# Sheet1.net
KiCad netlist of a schematic drawn in Altium Designer
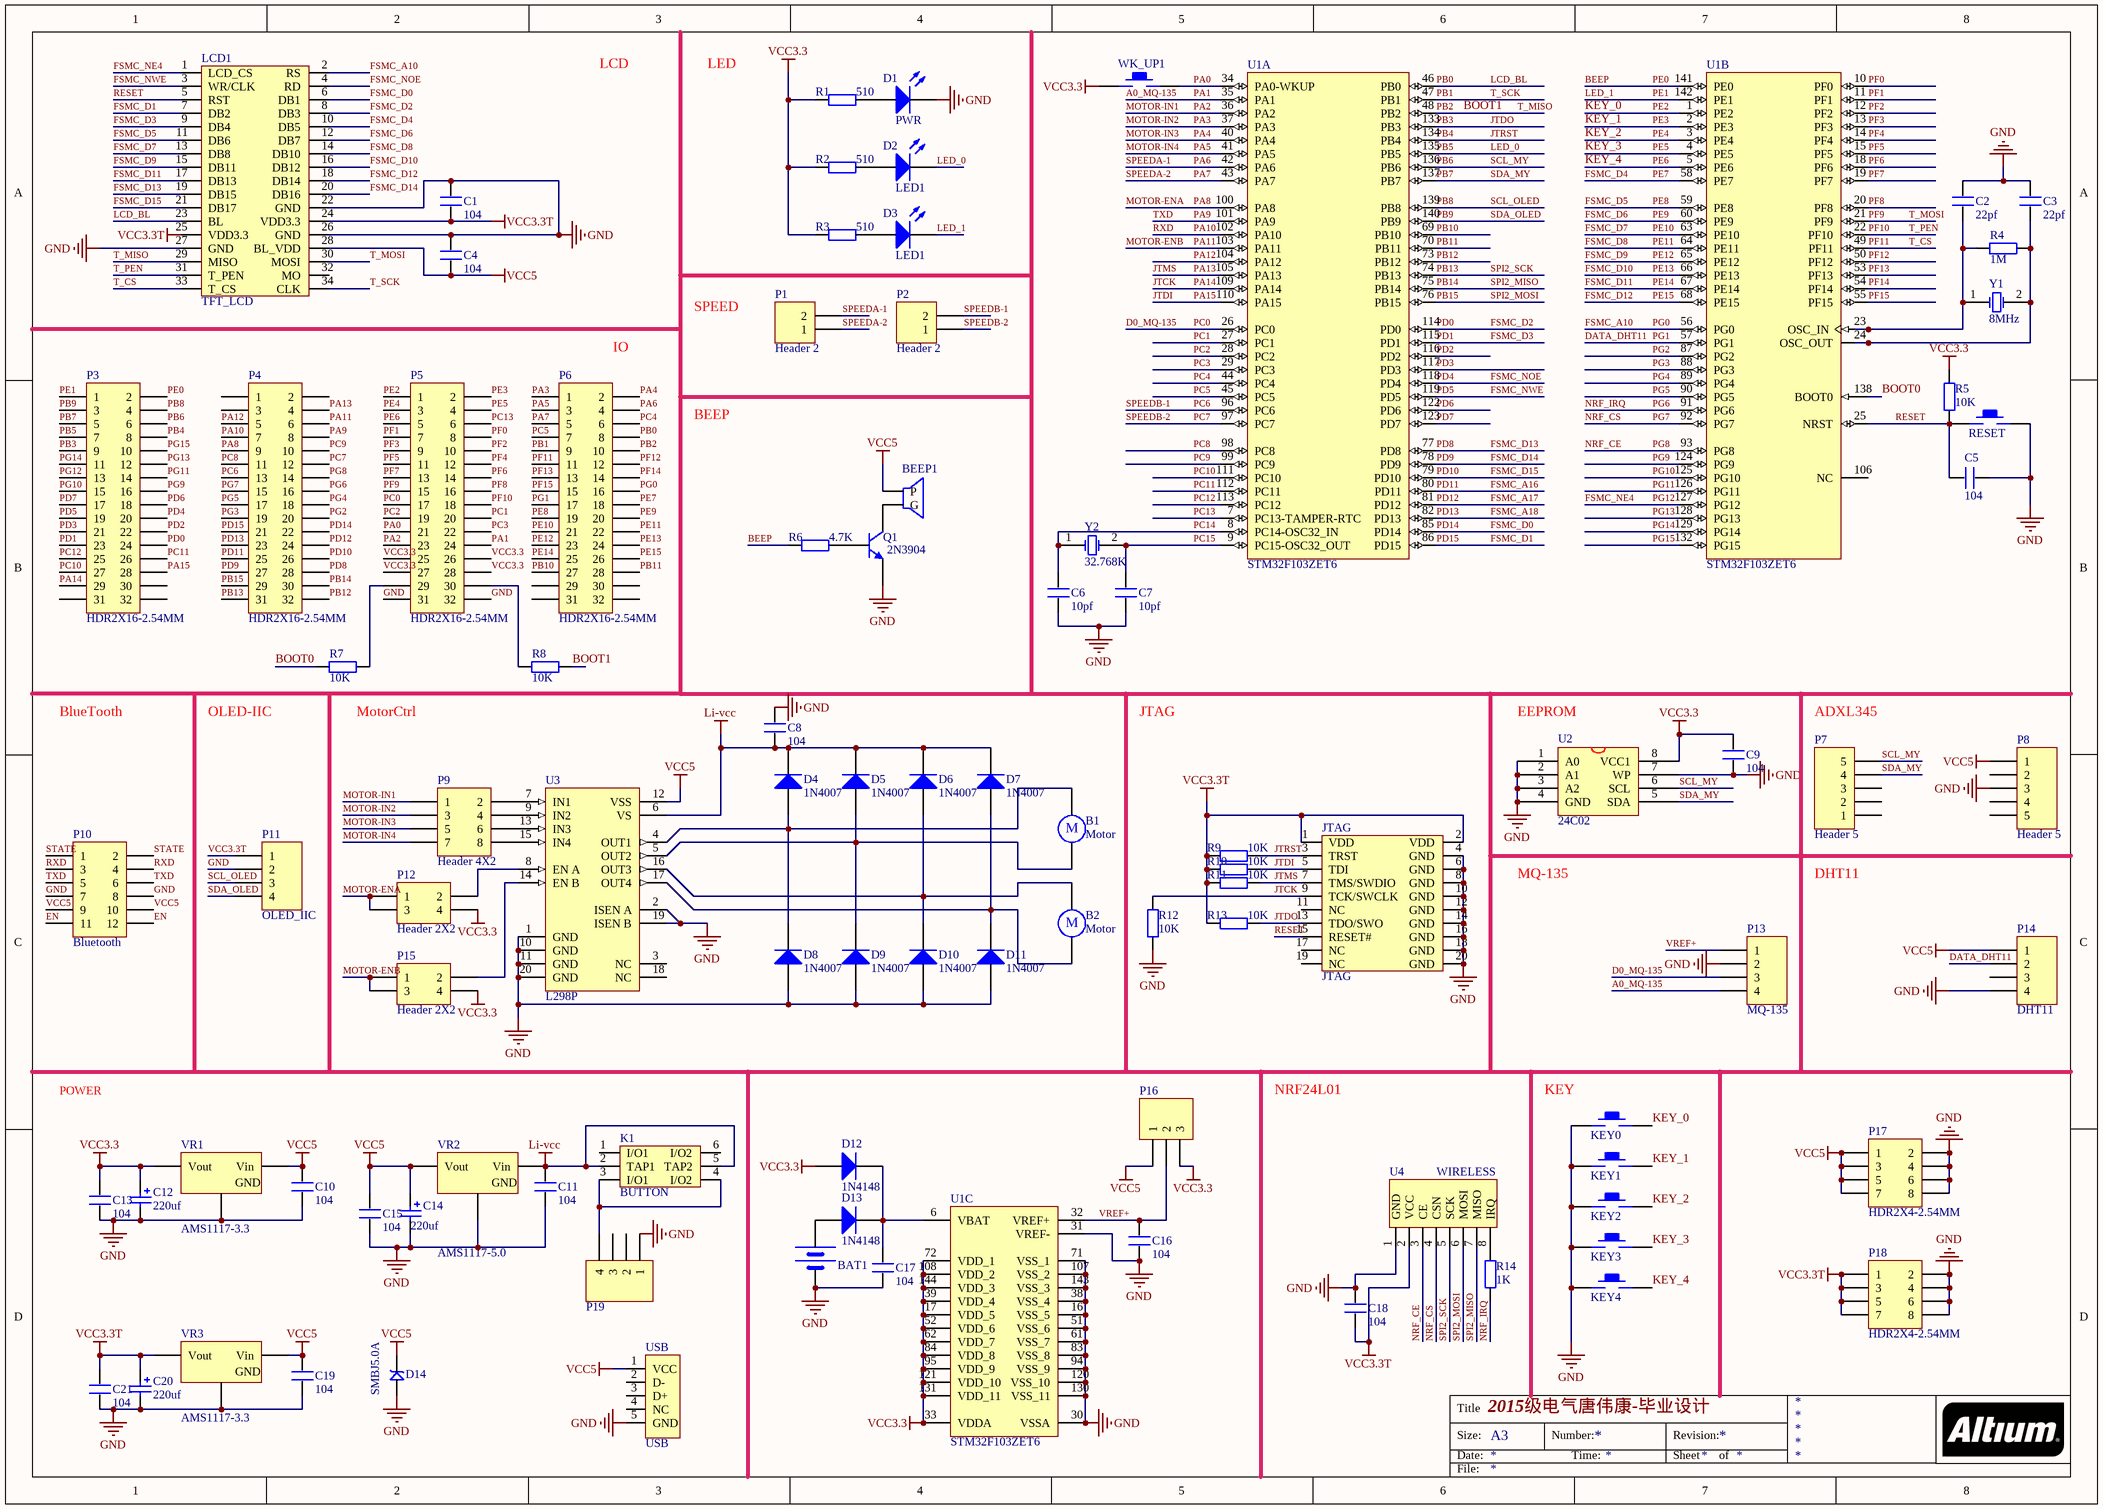
[diagram p0: Sheet1.SchDoc]

(export (version "E")
  (design (tool "Eeschema 10.0.6"))
  (components
    (comp (ref "B1")
      (value "Motor")
      (footprint "RB5-10.5")
      (description "Motor, General Kind")
      (fields (field (name "PUBLISHER") "Altium Limited"))
      (libsource (lib "Miscellaneous Devices") (part "Motor"))
    )
    (comp (ref "B2")
      (value "Motor")
      (footprint "RB5-10.5")
      (description "Motor, General Kind")
      (fields (field (name "PUBLISHER") "Altium Limited"))
      (libsource (lib "Miscellaneous Devices") (part "Motor"))
    )
    (comp (ref "BAT1") (value "BATT") (footprint "BATM") (libsource (lib "MiniSTM32 V3.0封装库") (part "BAT")))
    (comp (ref "BEEP1")
      (value "BEEP")
      (footprint "BELL-5")
      (libsource (lib "WarShip V3 STM32103封装库") (part "BEEP"))
    )
    (comp (ref "C1") (value "104") (footprint "0805") (libsource (lib "WarShip V3 STM32103封装库") (part "C")))
    (comp (ref "C2") (value "22pf") (footprint "0805") (libsource (lib "WarShip V3 STM32103封装库") (part "C")))
    (comp (ref "C3") (value "22pf") (footprint "0805") (libsource (lib "WarShip V3 STM32103封装库") (part "C")))
    (comp (ref "C4") (value "104") (footprint "0805") (libsource (lib "WarShip V3 STM32103封装库") (part "C")))
    (comp (ref "C5") (value "104") (footprint "0805") (libsource (lib "WarShip V3 STM32103封装库") (part "C")))
    (comp (ref "C6") (value "10pf") (footprint "0805") (libsource (lib "WarShip V3 STM32103封装库") (part "C")))
    (comp (ref "C7") (value "10pf") (footprint "0805") (libsource (lib "WarShip V3 STM32103封装库") (part "C")))
    (comp (ref "C8")
      (value "104")
      (footprint "0805")
      (description "10uf")
      (libsource (lib "WarShip V3 STM32103封装库") (part "C"))
    )
    (comp (ref "C9") (value "104") (footprint "0805") (libsource (lib "WarShip V3 STM32103封装库") (part "C")))
    (comp (ref "C10")
      (value "104")
      (footprint "0805")
      (description "10uf")
      (libsource (lib "WarShip V3 STM32103封装库") (part "C"))
    )
    (comp (ref "C11")
      (value "104")
      (footprint "0805")
      (description "10uf")
      (libsource (lib "WarShip V3 STM32103封装库") (part "C"))
    )
    (comp (ref "C12")
      (value "220uf")
      (footprint "C-DIP-6.3*15")
      (description "*C-DIP-6.3*15")
      (libsource (lib "直插电容 6.3x15封装") (part "C-DIP-6.3*15"))
    )
    (comp (ref "C13") (value "104") (footprint "0805") (libsource (lib "WarShip V3 STM32103封装库") (part "C")))
    (comp (ref "C14")
      (value "220uf")
      (footprint "C-DIP-6.3*15")
      (description "*C-DIP-6.3*15")
      (libsource (lib "直插电容 6.3x15封装") (part "C-DIP-6.3*15"))
    )
    (comp (ref "C15") (value "104") (footprint "0805") (libsource (lib "WarShip V3 STM32103封装库") (part "C")))
    (comp (ref "C16")
      (value "104")
      (footprint "0805")
      (description "10uf")
      (libsource (lib "WarShip V3 STM32103封装库") (part "C"))
    )
    (comp (ref "C17") (value "104") (footprint "0805") (libsource (lib "WarShip V3 STM32103封装库") (part "C")))
    (comp (ref "C18") (value "104") (footprint "0805") (libsource (lib "WarShip V3 STM32103封装库") (part "C")))
    (comp (ref "C19") (value "104") (footprint "0805") (libsource (lib "WarShip V3 STM32103封装库") (part "C")))
    (comp (ref "C20")
      (value "220uf")
      (footprint "C-DIP-6.3*15")
      (description "*C-DIP-6.3*15")
      (libsource (lib "直插电容 6.3x15封装") (part "C-DIP-6.3*15"))
    )
    (comp (ref "C21") (value "104") (footprint "0805") (libsource (lib "WarShip V3 STM32103封装库") (part "C")))
    (comp (ref "D1")
      (value "PWR")
      (footprint "LED-1")
      (description "Typical RED GaAs LED")
      (fields (field (name "PUBLISHER") "Altium Limited"))
      (libsource (lib "Miscellaneous Devices") (part "LED1"))
    )
    (comp (ref "D2")
      (value "LED1")
      (footprint "LED-1")
      (description "Typical RED GaAs LED")
      (fields (field (name "PUBLISHER") "Altium Limited"))
      (libsource (lib "Miscellaneous Devices") (part "LED1"))
    )
    (comp (ref "D3")
      (value "LED1")
      (footprint "LED-1")
      (description "Typical RED GaAs LED")
      (fields (field (name "PUBLISHER") "Altium Limited"))
      (libsource (lib "Miscellaneous Devices") (part "LED1"))
    )
    (comp (ref "D4")
      (value "1N4007")
      (footprint "DO-41")
      (description "1 Amp General Purpose Rectifier")
      (fields (field (name "PUBLISHER") "Altium Limited"))
      (libsource (lib "Miscellaneous Devices") (part "Diode 1N4007"))
    )
    (comp (ref "D5")
      (value "1N4007")
      (footprint "DO-41")
      (description "1 Amp General Purpose Rectifier")
      (fields (field (name "PUBLISHER") "Altium Limited"))
      (libsource (lib "Miscellaneous Devices") (part "Diode 1N4007"))
    )
    (comp (ref "D6")
      (value "1N4007")
      (footprint "DO-41")
      (description "1 Amp General Purpose Rectifier")
      (fields (field (name "PUBLISHER") "Altium Limited"))
      (libsource (lib "Miscellaneous Devices") (part "Diode 1N4007"))
    )
    (comp (ref "D7")
      (value "1N4007")
      (footprint "DO-41")
      (description "1 Amp General Purpose Rectifier")
      (fields (field (name "PUBLISHER") "Altium Limited"))
      (libsource (lib "Miscellaneous Devices") (part "Diode 1N4007"))
    )
    (comp (ref "D8")
      (value "1N4007")
      (footprint "DO-41")
      (description "1 Amp General Purpose Rectifier")
      (fields (field (name "PUBLISHER") "Altium Limited"))
      (libsource (lib "Miscellaneous Devices") (part "Diode 1N4007"))
    )
    (comp (ref "D9")
      (value "1N4007")
      (footprint "DO-41")
      (description "1 Amp General Purpose Rectifier")
      (fields (field (name "PUBLISHER") "Altium Limited"))
      (libsource (lib "Miscellaneous Devices") (part "Diode 1N4007"))
    )
    (comp (ref "D10")
      (value "1N4007")
      (footprint "DO-41")
      (description "1 Amp General Purpose Rectifier")
      (fields (field (name "PUBLISHER") "Altium Limited"))
      (libsource (lib "Miscellaneous Devices") (part "Diode 1N4007"))
    )
    (comp (ref "D11")
      (value "1N4007")
      (footprint "DO-41")
      (description "1 Amp General Purpose Rectifier")
      (fields (field (name "PUBLISHER") "Altium Limited"))
      (libsource (lib "Miscellaneous Devices") (part "Diode 1N4007"))
    )
    (comp (ref "D12")
      (value "1N4148")
      (footprint "DO-35")
      (description "High Conductance Fast Diode")
      (fields (field (name "PUBLISHER") "Altium Limited"))
      (libsource (lib "Miscellaneous Devices") (part "Diode 1N4148"))
    )
    (comp (ref "D13")
      (value "1N4148")
      (footprint "DO-35")
      (description "High Conductance Fast Diode")
      (fields (field (name "PUBLISHER") "Altium Limited"))
      (libsource (lib "Miscellaneous Devices") (part "Diode 1N4148"))
    )
    (comp (ref "D14")
      (value "SMBJ5.0A")
      (footprint "SMBJ")
      (description "TVS")
      (libsource (lib "MiniSTM32 V3.0封装库") (part "SMBJ"))
    )
    (comp (ref "JTAG")
      (value "JTAG")
      (footprint "JTAG_20")
      (libsource (lib "WarShip V3 STM32103封装库") (part "JTAG"))
    )
    (comp (ref "K1")
      (value "BUTTON")
      (footprint "BTN8.5*8.5")
      (libsource (lib "WarShip V3 STM32103封装库") (part "BUTTON"))
    )
    (comp (ref "KEY0")
      (value "KEY0")
      (footprint "KEY_M")
      (libsource (lib "MiniSTM32 V3.0封装库") (part "KEY_M"))
    )
    (comp (ref "KEY1")
      (value "KEY1")
      (footprint "KEY_M")
      (libsource (lib "MiniSTM32 V3.0封装库") (part "KEY_M"))
    )
    (comp (ref "KEY2")
      (value "KEY2")
      (footprint "KEY_M")
      (libsource (lib "MiniSTM32 V3.0封装库") (part "KEY_M"))
    )
    (comp (ref "KEY3")
      (value "KEY2")
      (footprint "KEY_M")
      (libsource (lib "MiniSTM32 V3.0封装库") (part "KEY_M"))
    )
    (comp (ref "KEY4")
      (value "KEY2")
      (footprint "KEY_M")
      (libsource (lib "MiniSTM32 V3.0封装库") (part "KEY_M"))
    )
    (comp (ref "LCD1")
      (value "TFT_LCD")
      (footprint "db2*17-4.3")
      (libsource (lib "WarShip V3 STM32103封装库") (part "TFT_LCD"))
    )
    (comp (ref "P1")
      (value "Header 2")
      (footprint "HDR1X2")
      (description "Header, 2-Pin")
      (fields (field (name "PUBLISHER") "Altium Limited"))
      (libsource (lib "Miscellaneous Connectors") (part "Header 2"))
    )
    (comp (ref "P2")
      (value "Header 2")
      (footprint "HDR1X2")
      (description "Header, 2-Pin")
      (fields (field (name "PUBLISHER") "Altium Limited"))
      (libsource (lib "Miscellaneous Connectors") (part "Header 2"))
    )
    (comp (ref "P3")
      (value "HDR2X16-2.54MM")
      (footprint "HDR2X16-2.54MM")
      (fields (field (name "DESIGNER") "www.dratk.com"))
      (libsource (lib "HDR2X16-2.54MM") (part "HDR2X16-2.54MM"))
    )
    (comp (ref "P4")
      (value "HDR2X16-2.54MM")
      (footprint "HDR2X16-2.54MM")
      (fields (field (name "DESIGNER") "www.dratk.com"))
      (libsource (lib "HDR2X16-2.54MM") (part "HDR2X16-2.54MM"))
    )
    (comp (ref "P5")
      (value "HDR2X16-2.54MM")
      (footprint "HDR2X16-2.54MM")
      (fields (field (name "DESIGNER") "www.dratk.com"))
      (libsource (lib "HDR2X16-2.54MM") (part "HDR2X16-2.54MM"))
    )
    (comp (ref "P6")
      (value "HDR2X16-2.54MM")
      (footprint "HDR2X16-2.54MM")
      (fields (field (name "DESIGNER") "www.dratk.com"))
      (libsource (lib "HDR2X16-2.54MM") (part "HDR2X16-2.54MM"))
    )
    (comp (ref "P7")
      (value "Header 5")
      (footprint "HDR1X5")
      (description "Header, 5-Pin")
      (fields (field (name "PUBLISHER") "Altium Limited"))
      (libsource (lib "Miscellaneous Connectors") (part "Header 5"))
    )
    (comp (ref "P8")
      (value "Header 5")
      (footprint "HDR1X5")
      (description "Header, 5-Pin")
      (fields (field (name "PUBLISHER") "Altium Limited"))
      (libsource (lib "") (part "Header 5_1"))
    )
    (comp (ref "P9")
      (value "Header 4X2")
      (footprint "HDR2X4")
      (description "Header, 4-Pin, Dual row")
      (fields (field (name "PUBLISHER") "Altium Limited"))
      (libsource (lib "Miscellaneous Connectors") (part "Header 4X2"))
    )
    (comp (ref "P10")
      (value "Bluetooth")
      (footprint "Header2X6-2.54MM")
      (fields (field (name "DESIGNER") "www.dratk.com"))
      (libsource (lib "Header2X6-2.54MM") (part "Header2X6-2.54MM"))
    )
    (comp (ref "P11")
      (value "OLED_IIC")
      (footprint "Header1X4-2.54MM")
      (fields (field (name "DESIGNER") "www.dratk.com"))
      (libsource (lib "Header1X4-2.54MM") (part "Header1X4-2.54MM"))
    )
    (comp (ref "P12")
      (value "Header 2X2")
      (footprint "HDR2X2")
      (description "Header, 2-Pin, Dual row")
      (fields (field (name "PUBLISHER") "Altium Limited"))
      (libsource (lib "Miscellaneous Connectors") (part "Header 2X2"))
    )
    (comp (ref "P13")
      (value "MQ-135")
      (footprint "Header1X4-2.54MM")
      (fields (field (name "DESIGNER") "www.dratk.com"))
      (libsource (lib "Header1X4-2.54MM") (part "Header1X4-2.54MM"))
    )
    (comp (ref "P14")
      (value "DHT11")
      (footprint "Header1X4-2.54MM")
      (fields (field (name "DESIGNER") "www.dratk.com"))
      (libsource (lib "Header1X4-2.54MM") (part "Header1X4-2.54MM"))
    )
    (comp (ref "P15")
      (value "Header 2X2")
      (footprint "HDR2X2")
      (description "Header, 2-Pin, Dual row")
      (fields (field (name "PUBLISHER") "Altium Limited"))
      (libsource (lib "Miscellaneous Connectors") (part "Header 2X2"))
    )
    (comp (ref "P16")
      (value "Header 3")
      (footprint "HDR1X3")
      (description "Header, 3-Pin")
      (fields (field (name "PUBLISHER") "Altium Limited"))
      (libsource (lib "Miscellaneous Connectors") (part "Header 3"))
    )
    (comp (ref "P17")
      (value "HDR2X4-2.54MM")
      (footprint "HDR2X4-2.54MM")
      (fields (field (name "DESIGNER") "www.dratk.com"))
      (libsource (lib "HDR2X4-2.54MM") (part "HDR2X4-2.54MM"))
    )
    (comp (ref "P18")
      (value "HDR2X4-2.54MM")
      (footprint "HDR2X4-2.54MM")
      (fields (field (name "DESIGNER") "www.dratk.com"))
      (libsource (lib "HDR2X4-2.54MM") (part "HDR2X4-2.54MM"))
    )
    (comp (ref "P19")
      (value "Header1X4-2.54MM")
      (footprint "Header1X4-2.54MM")
      (fields (field (name "DESIGNER") "www.dratk.com"))
      (libsource (lib "") (part "Header1X4-2.54MM_1"))
    )
    (comp (ref "Q1")
      (value "2N3904")
      (footprint "TO-92A")
      (description "NPN General Purpose Amplifier")
      (fields (field (name "PUBLISHER") "Altium Limited"))
      (libsource (lib "Miscellaneous Devices") (part "2N3904"))
    )
    (comp (ref "R1")
      (value "510")
      (footprint "AXIAL-0.4")
      (description "Resistor")
      (fields (field (name "Comment") "Res2") (field (name "PUBLISHER") "Altium Limited"))
      (libsource (lib "Miscellaneous Devices") (part "Res2"))
    )
    (comp (ref "R2")
      (value "510")
      (footprint "AXIAL-0.4")
      (description "Resistor")
      (fields (field (name "Comment") "Res2") (field (name "PUBLISHER") "Altium Limited"))
      (libsource (lib "Miscellaneous Devices") (part "Res2"))
    )
    (comp (ref "R3")
      (value "510")
      (footprint "AXIAL-0.4")
      (description "Resistor")
      (fields (field (name "Comment") "Res2") (field (name "PUBLISHER") "Altium Limited"))
      (libsource (lib "Miscellaneous Devices") (part "Res2"))
    )
    (comp (ref "R4")
      (value "1M")
      (footprint "AXIAL-0.4")
      (description "Resistor")
      (fields (field (name "Comment") "Res2") (field (name "PUBLISHER") "Altium Limited"))
      (libsource (lib "Miscellaneous Devices") (part "Res2"))
    )
    (comp (ref "R5")
      (value "10K")
      (footprint "AXIAL-0.4")
      (description "Resistor")
      (fields (field (name "Comment") "Res2") (field (name "PUBLISHER") "Altium Limited"))
      (libsource (lib "") (part "Res2_1"))
    )
    (comp (ref "R6")
      (value "4.7K")
      (footprint "AXIAL-0.4")
      (description "Resistor")
      (fields (field (name "Comment") "Res2") (field (name "PUBLISHER") "Altium Limited"))
      (libsource (lib "Miscellaneous Devices") (part "Res2"))
    )
    (comp (ref "R7")
      (value "10K")
      (footprint "AXIAL-0.4")
      (description "Resistor")
      (fields (field (name "Comment") "Res2") (field (name "PUBLISHER") "Altium Limited"))
      (libsource (lib "Miscellaneous Devices") (part "Res2"))
    )
    (comp (ref "R8")
      (value "10K")
      (footprint "AXIAL-0.4")
      (description "Resistor")
      (fields (field (name "Comment") "Res2") (field (name "PUBLISHER") "Altium Limited"))
      (libsource (lib "Miscellaneous Devices") (part "Res2"))
    )
    (comp (ref "R9")
      (value "10K")
      (footprint "AXIAL-0.4")
      (description "Resistor")
      (fields (field (name "Comment") "Res2") (field (name "PUBLISHER") "Altium Limited"))
      (libsource (lib "Miscellaneous Devices") (part "Res2"))
    )
    (comp (ref "R10")
      (value "10K")
      (footprint "AXIAL-0.4")
      (description "Resistor")
      (fields (field (name "Comment") "Res2") (field (name "PUBLISHER") "Altium Limited"))
      (libsource (lib "Miscellaneous Devices") (part "Res2"))
    )
    (comp (ref "R11")
      (value "10K")
      (footprint "AXIAL-0.4")
      (description "Resistor")
      (fields (field (name "Comment") "Res2") (field (name "PUBLISHER") "Altium Limited"))
      (libsource (lib "Miscellaneous Devices") (part "Res2"))
    )
    (comp (ref "R12")
      (value "10K")
      (footprint "AXIAL-0.4")
      (description "Resistor")
      (fields (field (name "Comment") "Res2") (field (name "PUBLISHER") "Altium Limited"))
      (libsource (lib "") (part "Res2_1"))
    )
    (comp (ref "R13")
      (value "10K")
      (footprint "AXIAL-0.4")
      (description "Resistor")
      (fields (field (name "Comment") "Res2") (field (name "PUBLISHER") "Altium Limited"))
      (libsource (lib "Miscellaneous Devices") (part "Res2"))
    )
    (comp (ref "R14")
      (value "1K")
      (footprint "AXIAL-0.4")
      (description "Resistor")
      (fields (field (name "Comment") "Res2") (field (name "PUBLISHER") "Altium Limited"))
      (libsource (lib "") (part "Res2_1"))
    )
    (comp (ref "RESET")
      (value "RESET")
      (footprint "KEY_M")
      (libsource (lib "MiniSTM32 V3.0封装库") (part "KEY_M"))
    )
    (comp (ref "U1")
      (value "STM32F103ZET6")
      (footprint "STM-LQFP144_N")
      (libsource (lib "STMicroelectronics STM32 F1") (part "STM32F103ZET6"))
    )
    (comp (ref "U2")
      (value "24C02")
      (footprint "SOP-8")
      (libsource (lib "WarShip V3 STM32103封装库") (part "24C256"))
    )
    (comp (ref "U3")
      (value "L298P")
      (footprint "PowerSO20_N")
      (description "Dual Full Bridge Driver")
      (fields (field (name "PUBLISHER") "Altium Limited"))
      (libsource (lib "ST Interface DC Motor Controller") (part "L298P"))
    )
    (comp (ref "U4")
      (value "WIRELESS")
      (footprint "NRF24L01")
      (libsource (lib "WarShip V3 STM32103封装库") (part "NRF24L01"))
    )
    (comp (ref "USB")
      (value "USB")
      (footprint "USB/SM0.8-6H5")
      (libsource (lib "WarShip V3 STM32103封装库") (part "USB5"))
    )
    (comp (ref "VR1")
      (value "AMS1117-3.3")
      (footprint "SOT-223")
      (description "低压差线性稳压(LDO)")
      (libsource (lib "Miscellaneous Devices LC") (part "SOT-223 AMS1117-3.3"))
    )
    (comp (ref "VR2")
      (value "AMS1117-5.0")
      (footprint "SOT-223")
      (description "低压差线性稳压(LDO)")
      (libsource (lib "Miscellaneous Devices LC") (part "SOT-223 AMS1117-5.0"))
    )
    (comp (ref "VR3")
      (value "AMS1117-3.3")
      (footprint "SOT-223")
      (description "低压差线性稳压(LDO)")
      (libsource (lib "Miscellaneous Devices LC") (part "SOT-223 AMS1117-3.3"))
    )
    (comp (ref "WK_UP1")
      (value "WK_UP")
      (footprint "KEY_M")
      (libsource (lib "MiniSTM32 V3.0封装库") (part "KEY_M"))
    )
    (comp (ref "Y1")
      (value "8MHz")
      (footprint "XTAL_US")
      (description "Crystal Oscillator")
      (fields (field (name "PUBLISHER") "Altium Limited"))
      (libsource (lib "WarShip V3 STM32103封装库") (part "XTAL"))
    )
    (comp (ref "Y2")
      (value "32.768K")
      (footprint "R38")
      (description "Crystal Oscillator")
      (fields (field (name "PUBLISHER") "Altium Limited"))
      (libsource (lib "Miscellaneous Devices") (part "XTAL"))
    )
  )
  (nets
    (net (code "1") (name "/A0_MQ-135") (class "Default")
      (node (ref "P13") (pin "4") (pinfunction "4_4") (pintype "passive"))
      (node (ref "P5") (pin "24") (pinfunction "24_24") (pintype "passive"))
      (node (ref "U1") (pin "35") (pinfunction "PA1_35") (pintype "bidirectional"))
    )
    (net (code "2") (name "/BEEP") (class "Default")
      (node (ref "P3") (pin "2") (pinfunction "2_2") (pintype "passive"))
      (node (ref "R6") (pin "2") (pinfunction "2_2") (pintype "passive"))
      (node (ref "U1") (pin "141") (pinfunction "PE0_141") (pintype "bidirectional"))
    )
    (net (code "3") (name "/BOOT0") (class "Default")
      (node (ref "R7") (pin "2") (pinfunction "2_2") (pintype "passive"))
      (node (ref "U1") (pin "138") (pinfunction "BOOT0_138") (pintype "input"))
    )
    (net (code "4") (name "/BOOT1") (class "Default")
      (node (ref "LCD1") (pin "29") (pinfunction "MISO_29") (pintype "passive"))
      (node (ref "P6") (pin "10") (pinfunction "10_10") (pintype "passive"))
      (node (ref "R8") (pin "1") (pinfunction "1_1") (pintype "passive"))
      (node (ref "U1") (pin "48") (pinfunction "PB2_48") (pintype "bidirectional"))
    )
    (net (code "5") (name "/D0_MQ-135") (class "Default")
      (node (ref "P13") (pin "3") (pinfunction "3_3") (pintype "passive"))
      (node (ref "P5") (pin "17") (pinfunction "17_17") (pintype "passive"))
      (node (ref "U1") (pin "26") (pinfunction "PC0_26") (pintype "bidirectional"))
    )
    (net (code "6") (name "/DATA_DHT11") (class "Default")
      (node (ref "P14") (pin "2") (pinfunction "2_2") (pintype "passive"))
      (node (ref "P6") (pin "17") (pinfunction "17_17") (pintype "passive"))
      (node (ref "U1") (pin "57") (pinfunction "PG1_57") (pintype "bidirectional"))
    )
    (net (code "7") (name "/EN") (class "Default")
      (node (ref "P10") (pin "11") (pinfunction "11_11") (pintype "passive"))
      (node (ref "P10") (pin "12") (pinfunction "12_12") (pintype "passive"))
    )
    (net (code "8") (name "/FSMC_A10") (class "Default")
      (node (ref "LCD1") (pin "2") (pinfunction "RS_2") (pintype "passive"))
      (node (ref "P6") (pin "16") (pinfunction "16_16") (pintype "passive"))
      (node (ref "U1") (pin "56") (pinfunction "PG0_56") (pintype "bidirectional"))
    )
    (net (code "9") (name "/FSMC_A16") (class "Default")
      (node (ref "P4") (pin "25") (pinfunction "25_25") (pintype "passive"))
      (node (ref "U1") (pin "80") (pinfunction "PD11_80") (pintype "bidirectional"))
    )
    (net (code "10") (name "/FSMC_A17") (class "Default")
      (node (ref "P4") (pin "24") (pinfunction "24_24") (pintype "passive"))
      (node (ref "U1") (pin "81") (pinfunction "PD12_81") (pintype "bidirectional"))
    )
    (net (code "11") (name "/FSMC_A18") (class "Default")
      (node (ref "P4") (pin "23") (pinfunction "23_23") (pintype "passive"))
      (node (ref "U1") (pin "82") (pinfunction "PD13_82") (pintype "bidirectional"))
    )
    (net (code "12") (name "/FSMC_D0") (class "Default")
      (node (ref "LCD1") (pin "6") (pinfunction "DB1_6") (pintype "passive"))
      (node (ref "P4") (pin "22") (pinfunction "22_22") (pintype "passive"))
      (node (ref "U1") (pin "85") (pinfunction "PD14_85") (pintype "bidirectional"))
    )
    (net (code "13") (name "/FSMC_D1") (class "Default")
      (node (ref "LCD1") (pin "7") (pinfunction "DB2_7") (pintype "passive"))
      (node (ref "P4") (pin "21") (pinfunction "21_21") (pintype "passive"))
      (node (ref "U1") (pin "86") (pinfunction "PD15_86") (pintype "bidirectional"))
    )
    (net (code "14") (name "/FSMC_D2") (class "Default")
      (node (ref "LCD1") (pin "8") (pinfunction "DB3_8") (pintype "passive"))
      (node (ref "P3") (pin "24") (pinfunction "24_24") (pintype "passive"))
      (node (ref "U1") (pin "114") (pinfunction "PD0_114") (pintype "bidirectional"))
    )
    (net (code "15") (name "/FSMC_D3") (class "Default")
      (node (ref "LCD1") (pin "9") (pinfunction "DB4_9") (pintype "passive"))
      (node (ref "P3") (pin "23") (pinfunction "23_23") (pintype "passive"))
      (node (ref "U1") (pin "115") (pinfunction "PD1_115") (pintype "bidirectional"))
    )
    (net (code "16") (name "/FSMC_D4") (class "Default")
      (node (ref "LCD1") (pin "10") (pinfunction "DB5_10") (pintype "passive"))
      (node (ref "P6") (pin "18") (pinfunction "18_18") (pintype "passive"))
      (node (ref "U1") (pin "58") (pinfunction "PE7_58") (pintype "bidirectional"))
    )
    (net (code "17") (name "/FSMC_D5") (class "Default")
      (node (ref "LCD1") (pin "11") (pinfunction "DB6_11") (pintype "passive"))
      (node (ref "P6") (pin "19") (pinfunction "19_19") (pintype "passive"))
      (node (ref "U1") (pin "59") (pinfunction "PE8_59") (pintype "bidirectional"))
    )
    (net (code "18") (name "/FSMC_D6") (class "Default")
      (node (ref "LCD1") (pin "12") (pinfunction "DB7_12") (pintype "passive"))
      (node (ref "P6") (pin "20") (pinfunction "20_20") (pintype "passive"))
      (node (ref "U1") (pin "60") (pinfunction "PE9_60") (pintype "bidirectional"))
    )
    (net (code "19") (name "/FSMC_D7") (class "Default")
      (node (ref "LCD1") (pin "13") (pinfunction "DB8_13") (pintype "passive"))
      (node (ref "P6") (pin "21") (pinfunction "21_21") (pintype "passive"))
      (node (ref "U1") (pin "63") (pinfunction "PE10_63") (pintype "bidirectional"))
    )
    (net (code "20") (name "/FSMC_D8") (class "Default")
      (node (ref "LCD1") (pin "14") (pinfunction "DB10_14") (pintype "passive"))
      (node (ref "P6") (pin "22") (pinfunction "22_22") (pintype "passive"))
      (node (ref "U1") (pin "64") (pinfunction "PE11_64") (pintype "bidirectional"))
    )
    (net (code "21") (name "/FSMC_D9") (class "Default")
      (node (ref "LCD1") (pin "15") (pinfunction "DB11_15") (pintype "passive"))
      (node (ref "P6") (pin "23") (pinfunction "23_23") (pintype "passive"))
      (node (ref "U1") (pin "65") (pinfunction "PE12_65") (pintype "bidirectional"))
    )
    (net (code "22") (name "/FSMC_D10") (class "Default")
      (node (ref "LCD1") (pin "16") (pinfunction "DB12_16") (pintype "passive"))
      (node (ref "P6") (pin "24") (pinfunction "24_24") (pintype "passive"))
      (node (ref "U1") (pin "66") (pinfunction "PE13_66") (pintype "bidirectional"))
    )
    (net (code "23") (name "/FSMC_D11") (class "Default")
      (node (ref "LCD1") (pin "17") (pinfunction "DB13_17") (pintype "passive"))
      (node (ref "P6") (pin "25") (pinfunction "25_25") (pintype "passive"))
      (node (ref "U1") (pin "67") (pinfunction "PE14_67") (pintype "bidirectional"))
    )
    (net (code "24") (name "/FSMC_D12") (class "Default")
      (node (ref "LCD1") (pin "18") (pinfunction "DB14_18") (pintype "passive"))
      (node (ref "P6") (pin "26") (pinfunction "26_26") (pintype "passive"))
      (node (ref "U1") (pin "68") (pinfunction "PE15_68") (pintype "bidirectional"))
    )
    (net (code "25") (name "/FSMC_D13") (class "Default")
      (node (ref "LCD1") (pin "19") (pinfunction "DB15_19") (pintype "passive"))
      (node (ref "P4") (pin "28") (pinfunction "28_28") (pintype "passive"))
      (node (ref "U1") (pin "77") (pinfunction "PD8_77") (pintype "bidirectional"))
    )
    (net (code "26") (name "/FSMC_D14") (class "Default")
      (node (ref "LCD1") (pin "20") (pinfunction "DB16_20") (pintype "passive"))
      (node (ref "P4") (pin "27") (pinfunction "27_27") (pintype "passive"))
      (node (ref "U1") (pin "78") (pinfunction "PD9_78") (pintype "bidirectional"))
    )
    (net (code "27") (name "/FSMC_D15") (class "Default")
      (node (ref "LCD1") (pin "21") (pinfunction "DB17_21") (pintype "passive"))
      (node (ref "P4") (pin "26") (pinfunction "26_26") (pintype "passive"))
      (node (ref "U1") (pin "79") (pinfunction "PD10_79") (pintype "bidirectional"))
    )
    (net (code "28") (name "/FSMC_NE4") (class "Default")
      (node (ref "LCD1") (pin "1") (pinfunction "LCD_CS_1") (pintype "passive"))
      (node (ref "P3") (pin "13") (pinfunction "13_13") (pintype "passive"))
      (node (ref "U1") (pin "127") (pinfunction "PG12_127") (pintype "bidirectional"))
    )
    (net (code "29") (name "/FSMC_NOE") (class "Default")
      (node (ref "LCD1") (pin "4") (pinfunction "RD_4") (pintype "passive"))
      (node (ref "P3") (pin "20") (pinfunction "20_20") (pintype "passive"))
      (node (ref "U1") (pin "118") (pinfunction "PD4_118") (pintype "bidirectional"))
    )
    (net (code "30") (name "/FSMC_NWE") (class "Default")
      (node (ref "LCD1") (pin "3") (pinfunction "WR/CLK_3") (pintype "passive"))
      (node (ref "P3") (pin "19") (pinfunction "19_19") (pintype "passive"))
      (node (ref "U1") (pin "119") (pinfunction "PD5_119") (pintype "bidirectional"))
    )
    (net (code "31") (name "/JTCK") (class "Default")
      (node (ref "JTAG") (pin "9") (pinfunction "TCK/SWCLK_9") (pintype "passive"))
      (node (ref "P3") (pin "29") (pinfunction "29_29") (pintype "passive"))
      (node (ref "R12") (pin "2") (pinfunction "2_2") (pintype "passive"))
      (node (ref "U1") (pin "109") (pinfunction "PA14_109") (pintype "bidirectional"))
    )
    (net (code "32") (name "/JTDI") (class "Default")
      (node (ref "JTAG") (pin "5") (pinfunction "TDI_5") (pintype "passive"))
      (node (ref "P3") (pin "28") (pinfunction "28_28") (pintype "passive"))
      (node (ref "R10") (pin "1") (pinfunction "1_1") (pintype "passive"))
      (node (ref "U1") (pin "110") (pinfunction "PA15_110") (pintype "bidirectional"))
    )
    (net (code "33") (name "/JTDO") (class "Default")
      (node (ref "JTAG") (pin "13") (pinfunction "TDO/SWO_13") (pintype "passive"))
      (node (ref "P3") (pin "9") (pinfunction "9_9") (pintype "passive"))
      (node (ref "R13") (pin "1") (pinfunction "1_1") (pintype "passive"))
      (node (ref "U1") (pin "133") (pinfunction "PB3_133") (pintype "bidirectional"))
    )
    (net (code "34") (name "/JTMS") (class "Default")
      (node (ref "JTAG") (pin "7") (pinfunction "TMS/SWDIO_7") (pintype "passive"))
      (node (ref "P4") (pin "4") (pinfunction "4_4") (pintype "passive"))
      (node (ref "R11") (pin "1") (pinfunction "1_1") (pintype "passive"))
      (node (ref "U1") (pin "105") (pinfunction "PA13_105") (pintype "bidirectional"))
    )
    (net (code "35") (name "/JTRST") (class "Default")
      (node (ref "JTAG") (pin "3") (pinfunction "TRST_3") (pintype "passive"))
      (node (ref "P3") (pin "8") (pinfunction "8_8") (pintype "passive"))
      (node (ref "R9") (pin "1") (pinfunction "1_1") (pintype "passive"))
      (node (ref "U1") (pin "134") (pinfunction "PB4_134") (pintype "bidirectional"))
    )
    (net (code "36") (name "/KEY_0") (class "Default")
      (node (ref "KEY0") (pin "2") (pinfunction "2_2") (pintype "passive"))
      (node (ref "P5") (pin "1") (pinfunction "1_1") (pintype "passive"))
      (node (ref "U1") (pin "1") (pinfunction "PE2_1") (pintype "bidirectional"))
    )
    (net (code "37") (name "/KEY_1") (class "Default")
      (node (ref "KEY1") (pin "2") (pinfunction "2_2") (pintype "passive"))
      (node (ref "P5") (pin "2") (pinfunction "2_2") (pintype "passive"))
      (node (ref "U1") (pin "2") (pinfunction "PE3_2") (pintype "bidirectional"))
    )
    (net (code "38") (name "/KEY_2") (class "Default")
      (node (ref "KEY2") (pin "2") (pinfunction "2_2") (pintype "passive"))
      (node (ref "P5") (pin "3") (pinfunction "3_3") (pintype "passive"))
      (node (ref "U1") (pin "3") (pinfunction "PE4_3") (pintype "bidirectional"))
    )
    (net (code "39") (name "/KEY_3") (class "Default")
      (node (ref "KEY3") (pin "2") (pinfunction "2_2") (pintype "passive"))
      (node (ref "P5") (pin "4") (pinfunction "4_4") (pintype "passive"))
      (node (ref "U1") (pin "4") (pinfunction "PE5_4") (pintype "bidirectional"))
    )
    (net (code "40") (name "/KEY_4") (class "Default")
      (node (ref "KEY4") (pin "2") (pinfunction "2_2") (pintype "passive"))
      (node (ref "P5") (pin "5") (pinfunction "5_5") (pintype "passive"))
      (node (ref "U1") (pin "5") (pinfunction "PE6_5") (pintype "bidirectional"))
    )
    (net (code "41") (name "/LCD_BL") (class "Default")
      (node (ref "LCD1") (pin "23") (pinfunction "BL_23") (pintype "passive"))
      (node (ref "P6") (pin "8") (pinfunction "8_8") (pintype "passive"))
      (node (ref "U1") (pin "46") (pinfunction "PB0_46") (pintype "bidirectional"))
    )
    (net (code "42") (name "/LED_0") (class "Default")
      (node (ref "D2") (pin "2") (pinfunction "K_2") (pintype "passive"))
      (node (ref "P3") (pin "7") (pinfunction "7_7") (pintype "passive"))
      (node (ref "U1") (pin "135") (pinfunction "PB5_135") (pintype "bidirectional"))
    )
    (net (code "43") (name "/LED_1") (class "Default")
      (node (ref "D3") (pin "2") (pinfunction "K_2") (pintype "passive"))
      (node (ref "P3") (pin "1") (pinfunction "1_1") (pintype "passive"))
      (node (ref "U1") (pin "142") (pinfunction "PE1_142") (pintype "bidirectional"))
    )
    (net (code "44") (name "/MOTOR-ENA") (class "Default")
      (node (ref "P12") (pin "1") (pinfunction "1_1") (pintype "passive"))
      (node (ref "P12") (pin "3") (pinfunction "3_3") (pintype "passive"))
      (node (ref "P4") (pin "9") (pinfunction "9_9") (pintype "passive"))
      (node (ref "U1") (pin "100") (pinfunction "PA8_100") (pintype "bidirectional"))
    )
    (net (code "45") (name "/MOTOR-ENB") (class "Default")
      (node (ref "P15") (pin "1") (pinfunction "1_1") (pintype "passive"))
      (node (ref "P15") (pin "3") (pinfunction "3_3") (pintype "passive"))
      (node (ref "P4") (pin "6") (pinfunction "6_6") (pintype "passive"))
      (node (ref "U1") (pin "103") (pinfunction "PA11_103") (pintype "bidirectional"))
    )
    (net (code "46") (name "/MOTOR-IN1") (class "Default")
      (node (ref "P5") (pin "23") (pinfunction "23_23") (pintype "passive"))
      (node (ref "P9") (pin "1") (pinfunction "1_1") (pintype "passive"))
      (node (ref "U1") (pin "36") (pinfunction "PA2_36") (pintype "bidirectional"))
    )
    (net (code "47") (name "/MOTOR-IN2") (class "Default")
      (node (ref "P6") (pin "1") (pinfunction "1_1") (pintype "passive"))
      (node (ref "P9") (pin "3") (pinfunction "3_3") (pintype "passive"))
      (node (ref "U1") (pin "37") (pinfunction "PA3_37") (pintype "bidirectional"))
    )
    (net (code "48") (name "/MOTOR-IN3") (class "Default")
      (node (ref "P6") (pin "2") (pinfunction "2_2") (pintype "passive"))
      (node (ref "P9") (pin "5") (pinfunction "5_5") (pintype "passive"))
      (node (ref "U1") (pin "40") (pinfunction "PA4_40") (pintype "bidirectional"))
    )
    (net (code "49") (name "/MOTOR-IN4") (class "Default")
      (node (ref "P6") (pin "3") (pinfunction "3_3") (pintype "passive"))
      (node (ref "P9") (pin "7") (pinfunction "7_7") (pintype "passive"))
      (node (ref "U1") (pin "41") (pinfunction "PA5_41") (pintype "bidirectional"))
    )
    (net (code "50") (name "/NRF_CE") (class "Default")
      (node (ref "P4") (pin "14") (pinfunction "14_14") (pintype "passive"))
      (node (ref "U1") (pin "93") (pinfunction "PG8_93") (pintype "bidirectional"))
      (node (ref "U4") (pin "3") (pinfunction "CE_3") (pintype "passive"))
    )
    (net (code "51") (name "/NRF_CS") (class "Default")
      (node (ref "P4") (pin "15") (pinfunction "15_15") (pintype "passive"))
      (node (ref "U1") (pin "92") (pinfunction "PG7_92") (pintype "bidirectional"))
      (node (ref "U4") (pin "4") (pinfunction "CSN_4") (pintype "passive"))
    )
    (net (code "52") (name "/NRF_IRQ") (class "Default")
      (node (ref "P4") (pin "16") (pinfunction "16_16") (pintype "passive"))
      (node (ref "R14") (pin "1") (pinfunction "1_1") (pintype "passive"))
      (node (ref "U1") (pin "91") (pinfunction "PG6_91") (pintype "bidirectional"))
    )
    (net (code "53") (name "/PA0") (class "Default")
      (node (ref "P5") (pin "21") (pinfunction "21_21") (pintype "passive"))
      (node (ref "U1") (pin "34") (pinfunction "PA0-WKUP_34") (pintype "bidirectional"))
      (node (ref "WK_UP1") (pin "2") (pinfunction "2_2") (pintype "passive"))
    )
    (net (code "54") (name "/PA6") (class "Default")
      (node (ref "P1") (pin "2") (pinfunction "2_2") (pintype "passive"))
      (node (ref "P6") (pin "4") (pinfunction "4_4") (pintype "passive"))
      (node (ref "U1") (pin "42") (pinfunction "PA6_42") (pintype "bidirectional"))
    )
    (net (code "55") (name "/PA7") (class "Default")
      (node (ref "P1") (pin "1") (pinfunction "1_1") (pintype "passive"))
      (node (ref "P6") (pin "5") (pinfunction "5_5") (pintype "passive"))
      (node (ref "U1") (pin "43") (pinfunction "PA7_43") (pintype "bidirectional"))
    )
    (net (code "56") (name "/PA9") (class "Default")
      (node (ref "P10") (pin "5") (pinfunction "5_5") (pintype "passive"))
      (node (ref "P10") (pin "6") (pinfunction "6_6") (pintype "passive"))
      (node (ref "P4") (pin "8") (pinfunction "8_8") (pintype "passive"))
      (node (ref "U1") (pin "101") (pinfunction "PA9_101") (pintype "bidirectional"))
    )
    (net (code "57") (name "/PA10") (class "Default")
      (node (ref "P10") (pin "3") (pinfunction "3_3") (pintype "passive"))
      (node (ref "P10") (pin "4") (pinfunction "4_4") (pintype "passive"))
      (node (ref "P4") (pin "7") (pinfunction "7_7") (pintype "passive"))
      (node (ref "U1") (pin "102") (pinfunction "PA10_102") (pintype "bidirectional"))
    )
    (net (code "58") (name "/PA12") (class "Default")
      (node (ref "P4") (pin "5") (pinfunction "5_5") (pintype "passive"))
      (node (ref "U1") (pin "104") (pinfunction "PA12_104") (pintype "bidirectional"))
    )
    (net (code "59") (name "/PB1") (class "Default")
      (node (ref "LCD1") (pin "34") (pinfunction "CLK_34") (pintype "passive"))
      (node (ref "P6") (pin "9") (pinfunction "9_9") (pintype "passive"))
      (node (ref "U1") (pin "47") (pinfunction "PB1_47") (pintype "bidirectional"))
    )
    (net (code "60") (name "/PB6") (class "Default")
      (node (ref "P3") (pin "6") (pinfunction "6_6") (pintype "passive"))
      (node (ref "P7") (pin "5") (pinfunction "5_5") (pintype "passive"))
      (node (ref "U1") (pin "136") (pinfunction "PB6_136") (pintype "bidirectional"))
      (node (ref "U2") (pin "6") (pinfunction "SCL_6") (pintype "passive"))
    )
    (net (code "61") (name "/PB7") (class "Default")
      (node (ref "P3") (pin "5") (pinfunction "5_5") (pintype "passive"))
      (node (ref "P7") (pin "4") (pinfunction "4_4") (pintype "passive"))
      (node (ref "U1") (pin "137") (pinfunction "PB7_137") (pintype "bidirectional"))
      (node (ref "U2") (pin "5") (pinfunction "SDA_5") (pintype "passive"))
    )
    (net (code "62") (name "/PB8") (class "Default")
      (node (ref "P11") (pin "3") (pinfunction "3_3") (pintype "passive"))
      (node (ref "P3") (pin "4") (pinfunction "4_4") (pintype "passive"))
      (node (ref "U1") (pin "139") (pinfunction "PB8_139") (pintype "bidirectional"))
    )
    (net (code "63") (name "/PB9") (class "Default")
      (node (ref "P11") (pin "4") (pinfunction "4_4") (pintype "passive"))
      (node (ref "P3") (pin "3") (pinfunction "3_3") (pintype "passive"))
      (node (ref "U1") (pin "140") (pinfunction "PB9_140") (pintype "bidirectional"))
    )
    (net (code "64") (name "/PB10") (class "Default")
      (node (ref "P6") (pin "27") (pinfunction "27_27") (pintype "passive"))
      (node (ref "U1") (pin "69") (pinfunction "PB10_69") (pintype "bidirectional"))
    )
    (net (code "65") (name "/PB11") (class "Default")
      (node (ref "P6") (pin "28") (pinfunction "28_28") (pintype "passive"))
      (node (ref "U1") (pin "70") (pinfunction "PB11_70") (pintype "bidirectional"))
    )
    (net (code "66") (name "/PB12") (class "Default")
      (node (ref "P4") (pin "32") (pinfunction "32_32") (pintype "passive"))
      (node (ref "U1") (pin "73") (pinfunction "PB12_73") (pintype "bidirectional"))
    )
    (net (code "67") (name "/PB13") (class "Default")
      (node (ref "P4") (pin "31") (pinfunction "31_31") (pintype "passive"))
      (node (ref "U1") (pin "74") (pinfunction "PB13_74") (pintype "bidirectional"))
      (node (ref "U4") (pin "5") (pinfunction "SCK_5") (pintype "passive"))
    )
    (net (code "68") (name "/PB14") (class "Default")
      (node (ref "P4") (pin "30") (pinfunction "30_30") (pintype "passive"))
      (node (ref "U1") (pin "75") (pinfunction "PB14_75") (pintype "bidirectional"))
      (node (ref "U4") (pin "7") (pinfunction "MISO_7") (pintype "passive"))
    )
    (net (code "69") (name "/PB15") (class "Default")
      (node (ref "P4") (pin "29") (pinfunction "29_29") (pintype "passive"))
      (node (ref "U1") (pin "76") (pinfunction "PB15_76") (pintype "bidirectional"))
      (node (ref "U4") (pin "6") (pinfunction "MOSI_6") (pintype "passive"))
    )
    (net (code "70") (name "/PC1") (class "Default")
      (node (ref "P5") (pin "20") (pinfunction "20_20") (pintype "passive"))
      (node (ref "U1") (pin "27") (pinfunction "PC1_27") (pintype "bidirectional"))
    )
    (net (code "71") (name "/PC2") (class "Default")
      (node (ref "P5") (pin "19") (pinfunction "19_19") (pintype "passive"))
      (node (ref "U1") (pin "28") (pinfunction "PC2_28") (pintype "bidirectional"))
    )
    (net (code "72") (name "/PC3") (class "Default")
      (node (ref "P5") (pin "22") (pinfunction "22_22") (pintype "passive"))
      (node (ref "U1") (pin "29") (pinfunction "PC3_29") (pintype "bidirectional"))
    )
    (net (code "73") (name "/PC4") (class "Default")
      (node (ref "P6") (pin "6") (pinfunction "6_6") (pintype "passive"))
      (node (ref "U1") (pin "44") (pinfunction "PC4_44") (pintype "bidirectional"))
    )
    (net (code "74") (name "/PC5") (class "Default")
      (node (ref "P6") (pin "7") (pinfunction "7_7") (pintype "passive"))
      (node (ref "U1") (pin "45") (pinfunction "PC5_45") (pintype "bidirectional"))
    )
    (net (code "75") (name "/PC6") (class "Default")
      (node (ref "P2") (pin "2") (pinfunction "2_2") (pintype "passive"))
      (node (ref "P4") (pin "13") (pinfunction "13_13") (pintype "passive"))
      (node (ref "U1") (pin "96") (pinfunction "PC6_96") (pintype "bidirectional"))
    )
    (net (code "76") (name "/PC7") (class "Default")
      (node (ref "P2") (pin "1") (pinfunction "1_1") (pintype "passive"))
      (node (ref "P4") (pin "12") (pinfunction "12_12") (pintype "passive"))
      (node (ref "U1") (pin "97") (pinfunction "PC7_97") (pintype "bidirectional"))
    )
    (net (code "77") (name "/PC8") (class "Default")
      (node (ref "P4") (pin "11") (pinfunction "11_11") (pintype "passive"))
      (node (ref "U1") (pin "98") (pinfunction "PC8_98") (pintype "bidirectional"))
    )
    (net (code "78") (name "/PC9") (class "Default")
      (node (ref "P4") (pin "10") (pinfunction "10_10") (pintype "passive"))
      (node (ref "U1") (pin "99") (pinfunction "PC9_99") (pintype "bidirectional"))
    )
    (net (code "79") (name "/PC10") (class "Default")
      (node (ref "P3") (pin "27") (pinfunction "27_27") (pintype "passive"))
      (node (ref "U1") (pin "111") (pinfunction "PC10_111") (pintype "bidirectional"))
    )
    (net (code "80") (name "/PC11") (class "Default")
      (node (ref "P3") (pin "26") (pinfunction "26_26") (pintype "passive"))
      (node (ref "U1") (pin "112") (pinfunction "PC11_112") (pintype "bidirectional"))
    )
    (net (code "81") (name "/PC12") (class "Default")
      (node (ref "P3") (pin "25") (pinfunction "25_25") (pintype "passive"))
      (node (ref "U1") (pin "113") (pinfunction "PC12_113") (pintype "bidirectional"))
    )
    (net (code "82") (name "/PC13") (class "Default")
      (node (ref "P5") (pin "6") (pinfunction "6_6") (pintype "passive"))
      (node (ref "U1") (pin "7") (pinfunction "PC13-TAMPER-RTC_7") (pintype "bidirectional"))
    )
    (net (code "83") (name "/PC14") (class "Default")
      (node (ref "C6") (pin "2") (pintype "passive"))
      (node (ref "U1") (pin "8") (pinfunction "PC14-OSC32_IN_8") (pintype "bidirectional"))
      (node (ref "Y2") (pin "1") (pinfunction "OSC1_1") (pintype "passive"))
    )
    (net (code "84") (name "/PC15") (class "Default")
      (node (ref "C7") (pin "2") (pintype "passive"))
      (node (ref "U1") (pin "9") (pinfunction "PC15-OSC32_OUT_9") (pintype "bidirectional"))
      (node (ref "Y2") (pin "2") (pinfunction "OSC2_2") (pintype "passive"))
    )
    (net (code "85") (name "/PD2") (class "Default")
      (node (ref "P3") (pin "22") (pinfunction "22_22") (pintype "passive"))
      (node (ref "U1") (pin "116") (pinfunction "PD2_116") (pintype "bidirectional"))
    )
    (net (code "86") (name "/PD3") (class "Default")
      (node (ref "P3") (pin "21") (pinfunction "21_21") (pintype "passive"))
      (node (ref "U1") (pin "117") (pinfunction "PD3_117") (pintype "bidirectional"))
    )
    (net (code "87") (name "/PD6") (class "Default")
      (node (ref "P3") (pin "18") (pinfunction "18_18") (pintype "passive"))
      (node (ref "U1") (pin "122") (pinfunction "PD6_122") (pintype "bidirectional"))
    )
    (net (code "88") (name "/PD7") (class "Default")
      (node (ref "P3") (pin "17") (pinfunction "17_17") (pintype "passive"))
      (node (ref "U1") (pin "123") (pinfunction "PD7_123") (pintype "bidirectional"))
    )
    (net (code "89") (name "/PF0") (class "Default")
      (node (ref "P5") (pin "8") (pinfunction "8_8") (pintype "passive"))
      (node (ref "U1") (pin "10") (pinfunction "PF0_10") (pintype "bidirectional"))
    )
    (net (code "90") (name "/PF1") (class "Default")
      (node (ref "P5") (pin "7") (pinfunction "7_7") (pintype "passive"))
      (node (ref "U1") (pin "11") (pinfunction "PF1_11") (pintype "bidirectional"))
    )
    (net (code "91") (name "/PF2") (class "Default")
      (node (ref "P5") (pin "10") (pinfunction "10_10") (pintype "passive"))
      (node (ref "U1") (pin "12") (pinfunction "PF2_12") (pintype "bidirectional"))
    )
    (net (code "92") (name "/PF3") (class "Default")
      (node (ref "P5") (pin "9") (pinfunction "9_9") (pintype "passive"))
      (node (ref "U1") (pin "13") (pinfunction "PF3_13") (pintype "bidirectional"))
    )
    (net (code "93") (name "/PF4") (class "Default")
      (node (ref "P5") (pin "12") (pinfunction "12_12") (pintype "passive"))
      (node (ref "U1") (pin "14") (pinfunction "PF4_14") (pintype "bidirectional"))
    )
    (net (code "94") (name "/PF5") (class "Default")
      (node (ref "P5") (pin "11") (pinfunction "11_11") (pintype "passive"))
      (node (ref "U1") (pin "15") (pinfunction "PF5_15") (pintype "bidirectional"))
    )
    (net (code "95") (name "/PF6") (class "Default")
      (node (ref "P5") (pin "14") (pinfunction "14_14") (pintype "passive"))
      (node (ref "U1") (pin "18") (pinfunction "PF6_18") (pintype "bidirectional"))
    )
    (net (code "96") (name "/PF7") (class "Default")
      (node (ref "P5") (pin "13") (pinfunction "13_13") (pintype "passive"))
      (node (ref "U1") (pin "19") (pinfunction "PF7_19") (pintype "bidirectional"))
    )
    (net (code "97") (name "/PF8") (class "Default")
      (node (ref "P5") (pin "16") (pinfunction "16_16") (pintype "passive"))
      (node (ref "U1") (pin "20") (pinfunction "PF8_20") (pintype "bidirectional"))
    )
    (net (code "98") (name "/PF9") (class "Default")
      (node (ref "LCD1") (pin "30") (pinfunction "MOSI_30") (pintype "passive"))
      (node (ref "P5") (pin "15") (pinfunction "15_15") (pintype "passive"))
      (node (ref "U1") (pin "21") (pinfunction "PF9_21") (pintype "bidirectional"))
    )
    (net (code "99") (name "/PF10") (class "Default")
      (node (ref "LCD1") (pin "31") (pinfunction "T_PEN_31") (pintype "passive"))
      (node (ref "P5") (pin "18") (pinfunction "18_18") (pintype "passive"))
      (node (ref "U1") (pin "22") (pinfunction "PF10_22") (pintype "bidirectional"))
    )
    (net (code "100") (name "/PF11") (class "Default")
      (node (ref "LCD1") (pin "33") (pinfunction "T_CS_33") (pintype "passive"))
      (node (ref "P6") (pin "11") (pinfunction "11_11") (pintype "passive"))
      (node (ref "U1") (pin "49") (pinfunction "PF11_49") (pintype "bidirectional"))
    )
    (net (code "101") (name "/PF12") (class "Default")
      (node (ref "P6") (pin "12") (pinfunction "12_12") (pintype "passive"))
      (node (ref "U1") (pin "50") (pinfunction "PF12_50") (pintype "bidirectional"))
    )
    (net (code "102") (name "/PF13") (class "Default")
      (node (ref "P6") (pin "13") (pinfunction "13_13") (pintype "passive"))
      (node (ref "U1") (pin "53") (pinfunction "PF13_53") (pintype "bidirectional"))
    )
    (net (code "103") (name "/PF14") (class "Default")
      (node (ref "P6") (pin "14") (pinfunction "14_14") (pintype "passive"))
      (node (ref "U1") (pin "54") (pinfunction "PF14_54") (pintype "bidirectional"))
    )
    (net (code "104") (name "/PF15") (class "Default")
      (node (ref "P6") (pin "15") (pinfunction "15_15") (pintype "passive"))
      (node (ref "U1") (pin "55") (pinfunction "PF15_55") (pintype "bidirectional"))
    )
    (net (code "105") (name "/PG2") (class "Default")
      (node (ref "P4") (pin "20") (pinfunction "20_20") (pintype "passive"))
      (node (ref "U1") (pin "87") (pinfunction "PG2_87") (pintype "bidirectional"))
    )
    (net (code "106") (name "/PG3") (class "Default")
      (node (ref "P4") (pin "19") (pinfunction "19_19") (pintype "passive"))
      (node (ref "U1") (pin "88") (pinfunction "PG3_88") (pintype "bidirectional"))
    )
    (net (code "107") (name "/PG4") (class "Default")
      (node (ref "P4") (pin "18") (pinfunction "18_18") (pintype "passive"))
      (node (ref "U1") (pin "89") (pinfunction "PG4_89") (pintype "bidirectional"))
    )
    (net (code "108") (name "/PG5") (class "Default")
      (node (ref "P4") (pin "17") (pinfunction "17_17") (pintype "passive"))
      (node (ref "U1") (pin "90") (pinfunction "PG5_90") (pintype "bidirectional"))
    )
    (net (code "109") (name "/PG9") (class "Default")
      (node (ref "P3") (pin "16") (pinfunction "16_16") (pintype "passive"))
      (node (ref "U1") (pin "124") (pinfunction "PG9_124") (pintype "bidirectional"))
    )
    (net (code "110") (name "/PG10") (class "Default")
      (node (ref "P3") (pin "15") (pinfunction "15_15") (pintype "passive"))
      (node (ref "U1") (pin "125") (pinfunction "PG10_125") (pintype "bidirectional"))
    )
    (net (code "111") (name "/PG11") (class "Default")
      (node (ref "P3") (pin "14") (pinfunction "14_14") (pintype "passive"))
      (node (ref "U1") (pin "126") (pinfunction "PG11_126") (pintype "bidirectional"))
    )
    (net (code "112") (name "/PG13") (class "Default")
      (node (ref "P3") (pin "12") (pinfunction "12_12") (pintype "passive"))
      (node (ref "U1") (pin "128") (pinfunction "PG13_128") (pintype "bidirectional"))
    )
    (net (code "113") (name "/PG14") (class "Default")
      (node (ref "P3") (pin "11") (pinfunction "11_11") (pintype "passive"))
      (node (ref "U1") (pin "129") (pinfunction "PG14_129") (pintype "bidirectional"))
    )
    (net (code "114") (name "/PG15") (class "Default")
      (node (ref "P3") (pin "10") (pinfunction "10_10") (pintype "passive"))
      (node (ref "U1") (pin "132") (pinfunction "PG15_132") (pintype "bidirectional"))
    )
    (net (code "115") (name "/RESET") (class "Default")
      (node (ref "C5") (pin "1") (pintype "passive"))
      (node (ref "JTAG") (pin "15") (pinfunction "RESET#_15") (pintype "passive"))
      (node (ref "LCD1") (pin "5") (pinfunction "RST_5") (pintype "passive"))
      (node (ref "R5") (pin "1") (pinfunction "1_1") (pintype "passive"))
      (node (ref "RESET") (pin "1") (pinfunction "1_1") (pintype "passive"))
      (node (ref "U1") (pin "25") (pinfunction "NRST_25") (pintype "bidirectional"))
    )
    (net (code "116") (name "/STATE") (class "Default")
      (node (ref "P10") (pin "1") (pinfunction "1_1") (pintype "passive"))
      (node (ref "P10") (pin "2") (pinfunction "2_2") (pintype "passive"))
    )
    (net (code "117") (name "/VREF+") (class "Default")
      (node (ref "C16") (pin "2") (pintype "passive"))
      (node (ref "P13") (pin "1") (pinfunction "1_1") (pintype "passive"))
      (node (ref "P16") (pin "2") (pinfunction "2_2") (pintype "passive"))
      (node (ref "U1") (pin "32") (pinfunction "VREF+_32") (pintype "power_in"))
    )
    (net (code "118") (name "GND") (class "Default")
      (node (ref "BAT1") (pin "2") (pinfunction "GND_2") (pintype "passive"))
      (node (ref "C1") (pin "2") (pintype "passive"))
      (node (ref "C10") (pin "1") (pintype "passive"))
      (node (ref "C11") (pin "1") (pintype "passive"))
      (node (ref "C12") (pin "2") (pinfunction "2_2") (pintype "passive"))
      (node (ref "C13") (pin "1") (pintype "passive"))
      (node (ref "C14") (pin "2") (pinfunction "2_2") (pintype "passive"))
      (node (ref "C15") (pin "1") (pintype "passive"))
      (node (ref "C16") (pin "1") (pintype "passive"))
      (node (ref "C17") (pin "1") (pintype "passive"))
      (node (ref "C18") (pin "1") (pintype "passive"))
      (node (ref "C19") (pin "1") (pintype "passive"))
      (node (ref "C2") (pin "2") (pintype "passive"))
      (node (ref "C20") (pin "2") (pinfunction "2_2") (pintype "passive"))
      (node (ref "C21") (pin "1") (pintype "passive"))
      (node (ref "C3") (pin "2") (pintype "passive"))
      (node (ref "C4") (pin "2") (pintype "passive"))
      (node (ref "C5") (pin "2") (pintype "passive"))
      (node (ref "C6") (pin "1") (pintype "passive"))
      (node (ref "C7") (pin "1") (pintype "passive"))
      (node (ref "C8") (pin "2") (pintype "passive"))
      (node (ref "C9") (pin "2") (pintype "passive"))
      (node (ref "D1") (pin "2") (pinfunction "K_2") (pintype "passive"))
      (node (ref "D10") (pin "1") (pinfunction "A_1") (pintype "passive"))
      (node (ref "D11") (pin "1") (pinfunction "A_1") (pintype "passive"))
      (node (ref "D14") (pin "1") (pintype "passive"))
      (node (ref "D8") (pin "1") (pinfunction "A_1") (pintype "passive"))
      (node (ref "D9") (pin "1") (pinfunction "A_1") (pintype "passive"))
      (node (ref "JTAG") (pin "10") (pinfunction "GND_10") (pintype "passive"))
      (node (ref "JTAG") (pin "12") (pinfunction "GND_12") (pintype "passive"))
      (node (ref "JTAG") (pin "14") (pinfunction "GND_14") (pintype "passive"))
      (node (ref "JTAG") (pin "16") (pinfunction "GND_16") (pintype "passive"))
      (node (ref "JTAG") (pin "18") (pinfunction "GND_18") (pintype "passive"))
      (node (ref "JTAG") (pin "20") (pinfunction "GND_20") (pintype "passive"))
      (node (ref "JTAG") (pin "4") (pinfunction "GND_4") (pintype "passive"))
      (node (ref "JTAG") (pin "6") (pinfunction "GND_6") (pintype "passive"))
      (node (ref "JTAG") (pin "8") (pinfunction "GND_8") (pintype "passive"))
      (node (ref "KEY0") (pin "1") (pinfunction "1_1") (pintype "passive"))
      (node (ref "KEY1") (pin "1") (pinfunction "1_1") (pintype "passive"))
      (node (ref "KEY2") (pin "1") (pinfunction "1_1") (pintype "passive"))
      (node (ref "KEY3") (pin "1") (pinfunction "1_1") (pintype "passive"))
      (node (ref "KEY4") (pin "1") (pinfunction "1_1") (pintype "passive"))
      (node (ref "LCD1") (pin "22") (pinfunction "GND_22") (pintype "passive"))
      (node (ref "LCD1") (pin "26") (pinfunction "GND_26") (pintype "passive"))
      (node (ref "LCD1") (pin "27") (pinfunction "GND_27") (pintype "passive"))
      (node (ref "P10") (pin "7") (pinfunction "7_7") (pintype "passive"))
      (node (ref "P10") (pin "8") (pinfunction "8_8") (pintype "passive"))
      (node (ref "P11") (pin "2") (pinfunction "2_2") (pintype "passive"))
      (node (ref "P13") (pin "2") (pinfunction "2_2") (pintype "passive"))
      (node (ref "P14") (pin "4") (pinfunction "4_4") (pintype "passive"))
      (node (ref "P17") (pin "2") (pinfunction "2_2") (pintype "passive"))
      (node (ref "P17") (pin "4") (pinfunction "4_4") (pintype "passive"))
      (node (ref "P17") (pin "6") (pinfunction "6_6") (pintype "passive"))
      (node (ref "P17") (pin "8") (pinfunction "8_8") (pintype "passive"))
      (node (ref "P18") (pin "2") (pinfunction "2_2") (pintype "passive"))
      (node (ref "P18") (pin "4") (pinfunction "4_4") (pintype "passive"))
      (node (ref "P18") (pin "6") (pinfunction "6_6") (pintype "passive"))
      (node (ref "P18") (pin "8") (pinfunction "8_8") (pintype "passive"))
      (node (ref "P19") (pin "1") (pinfunction "1_1") (pintype "passive"))
      (node (ref "P5") (pin "31") (pinfunction "31_31") (pintype "passive"))
      (node (ref "P5") (pin "32") (pinfunction "32_32") (pintype "passive"))
      (node (ref "P8") (pin "3") (pinfunction "3_3") (pintype "passive"))
      (node (ref "Q1") (pin "1") (pinfunction "E_1") (pintype "passive"))
      (node (ref "R12") (pin "1") (pinfunction "1_1") (pintype "passive"))
      (node (ref "RESET") (pin "2") (pinfunction "2_2") (pintype "passive"))
      (node (ref "U1") (pin "107") (pinfunction "VSS_2_107") (pintype "power_in"))
      (node (ref "U1") (pin "120") (pinfunction "VSS_10_120") (pintype "power_in"))
      (node (ref "U1") (pin "130") (pinfunction "VSS_11_130") (pintype "power_in"))
      (node (ref "U1") (pin "143") (pinfunction "VSS_3_143") (pintype "power_in"))
      (node (ref "U1") (pin "16") (pinfunction "VSS_5_16") (pintype "power_in"))
      (node (ref "U1") (pin "30") (pinfunction "VSSA_30") (pintype "power_in"))
      (node (ref "U1") (pin "31") (pinfunction "VREF-_31") (pintype "power_in"))
      (node (ref "U1") (pin "38") (pinfunction "VSS_4_38") (pintype "power_in"))
      (node (ref "U1") (pin "51") (pinfunction "VSS_6_51") (pintype "power_in"))
      (node (ref "U1") (pin "61") (pinfunction "VSS_7_61") (pintype "power_in"))
      (node (ref "U1") (pin "71") (pinfunction "VSS_1_71") (pintype "power_in"))
      (node (ref "U1") (pin "83") (pinfunction "VSS_8_83") (pintype "power_in"))
      (node (ref "U1") (pin "94") (pinfunction "VSS_9_94") (pintype "power_in"))
      (node (ref "U2") (pin "1") (pinfunction "A0_1") (pintype "passive"))
      (node (ref "U2") (pin "2") (pinfunction "A1_2") (pintype "passive"))
      (node (ref "U2") (pin "3") (pinfunction "A2_3") (pintype "passive"))
      (node (ref "U2") (pin "4") (pinfunction "GND_4") (pintype "passive"))
      (node (ref "U2") (pin "7") (pinfunction "WP_7") (pintype "passive"))
      (node (ref "U3") (pin "1") (pinfunction "GND_1") (pintype "power_in"))
      (node (ref "U3") (pin "10") (pinfunction "GND_10") (pintype "power_in"))
      (node (ref "U3") (pin "11") (pinfunction "GND_11") (pintype "power_in"))
      (node (ref "U3") (pin "19") (pinfunction "ISEN_B_19") (pintype "passive"))
      (node (ref "U3") (pin "2") (pinfunction "ISEN_A_2") (pintype "passive"))
      (node (ref "U3") (pin "20") (pinfunction "GND_20") (pintype "power_in"))
      (node (ref "U4") (pin "1") (pinfunction "GND_1") (pintype "passive"))
      (node (ref "USB") (pin "5") (pinfunction "GND_5") (pintype "passive"))
      (node (ref "VR1") (pin "1") (pinfunction "GND_1") (pintype "passive"))
      (node (ref "VR2") (pin "1") (pinfunction "GND_1") (pintype "passive"))
      (node (ref "VR3") (pin "1") (pinfunction "GND_1") (pintype "passive"))
    )
    (net (code "119") (name "Li-vcc") (class "Default")
      (node (ref "C11") (pin "2") (pintype "passive"))
      (node (ref "C8") (pin "1") (pintype "passive"))
      (node (ref "D4") (pin "2") (pinfunction "K_2") (pintype "passive"))
      (node (ref "D5") (pin "2") (pinfunction "K_2") (pintype "passive"))
      (node (ref "D6") (pin "2") (pinfunction "K_2") (pintype "passive"))
      (node (ref "D7") (pin "2") (pinfunction "K_2") (pintype "passive"))
      (node (ref "K1") (pin "2") (pinfunction "TAP1_2") (pintype "passive"))
      (node (ref "K1") (pin "5") (pinfunction "TAP2_5") (pintype "passive"))
      (node (ref "U3") (pin "6") (pinfunction "VS_6") (pintype "power_in"))
      (node (ref "VR2") (pin "3") (pinfunction "Vin_3") (pintype "passive"))
    )
    (net (code "120") (name "Net-(BAT1-VCC)") (class "Default")
      (node (ref "BAT1") (pin "1") (pinfunction "VCC_1") (pintype "passive"))
      (node (ref "D13") (pin "1") (pinfunction "A_1") (pintype "passive"))
    )
    (net (code "121") (name "Net-(BEEP1-G)") (class "Default")
      (node (ref "BEEP1") (pin "2") (pinfunction "G_2") (pintype "passive"))
      (node (ref "Q1") (pin "3") (pinfunction "C_3") (pintype "passive"))
    )
    (net (code "122") (name "Net-(D1-A)") (class "Default")
      (node (ref "D1") (pin "1") (pinfunction "A_1") (pintype "passive"))
      (node (ref "R1") (pin "1") (pinfunction "1_1") (pintype "passive"))
    )
    (net (code "123") (name "Net-(D2-A)") (class "Default")
      (node (ref "D2") (pin "1") (pinfunction "A_1") (pintype "passive"))
      (node (ref "R2") (pin "1") (pinfunction "1_1") (pintype "passive"))
    )
    (net (code "124") (name "Net-(D3-A)") (class "Default")
      (node (ref "D3") (pin "1") (pinfunction "A_1") (pintype "passive"))
      (node (ref "R3") (pin "1") (pinfunction "1_1") (pintype "passive"))
    )
    (net (code "125") (name "Net-(D4-A)") (class "Default")
      (node (ref "B1") (pin "1") (pinfunction "1_1") (pintype "passive"))
      (node (ref "D4") (pin "1") (pinfunction "A_1") (pintype "passive"))
      (node (ref "D8") (pin "2") (pinfunction "K_2") (pintype "passive"))
      (node (ref "U3") (pin "4") (pinfunction "OUT1_4") (pintype "output"))
    )
    (net (code "126") (name "Net-(D5-A)") (class "Default")
      (node (ref "B1") (pin "2") (pinfunction "2_2") (pintype "passive"))
      (node (ref "D5") (pin "1") (pinfunction "A_1") (pintype "passive"))
      (node (ref "D9") (pin "2") (pinfunction "K_2") (pintype "passive"))
      (node (ref "U3") (pin "5") (pinfunction "OUT2_5") (pintype "output"))
    )
    (net (code "127") (name "Net-(D10-K)") (class "Default")
      (node (ref "B2") (pin "1") (pinfunction "1_1") (pintype "passive"))
      (node (ref "D10") (pin "2") (pinfunction "K_2") (pintype "passive"))
      (node (ref "D6") (pin "1") (pinfunction "A_1") (pintype "passive"))
      (node (ref "U3") (pin "16") (pinfunction "OUT3_16") (pintype "output"))
    )
    (net (code "128") (name "Net-(D11-K)") (class "Default")
      (node (ref "B2") (pin "2") (pinfunction "2_2") (pintype "passive"))
      (node (ref "D11") (pin "2") (pinfunction "K_2") (pintype "passive"))
      (node (ref "D7") (pin "1") (pinfunction "A_1") (pintype "passive"))
      (node (ref "U3") (pin "17") (pinfunction "OUT4_17") (pintype "output"))
    )
    (net (code "129") (name "Net-(D12-K)") (class "Default")
      (node (ref "C17") (pin "2") (pintype "passive"))
      (node (ref "D12") (pin "2") (pinfunction "K_2") (pintype "passive"))
      (node (ref "D13") (pin "2") (pinfunction "K_2") (pintype "passive"))
      (node (ref "U1") (pin "6") (pinfunction "VBAT_6") (pintype "power_in"))
    )
    (net (code "130") (name "Net-(K1-I{slash}O1-Pad3)") (class "Default")
      (node (ref "K1") (pin "3") (pinfunction "I/O1_3") (pintype "passive"))
      (node (ref "K1") (pin "4") (pinfunction "I/O2_4") (pintype "passive"))
      (node (ref "P19") (pin "4") (pinfunction "4_4") (pintype "passive"))
    )
    (net (code "131") (name "Net-(P5-Pad29)") (class "Default")
      (node (ref "P5") (pin "29") (pinfunction "29_29") (pintype "passive"))
      (node (ref "R7") (pin "1") (pinfunction "1_1") (pintype "passive"))
    )
    (net (code "132") (name "Net-(P5-Pad30)") (class "Default")
      (node (ref "P5") (pin "30") (pinfunction "30_30") (pintype "passive"))
      (node (ref "R8") (pin "2") (pinfunction "2_2") (pintype "passive"))
    )
    (net (code "133") (name "Net-(Q1-B)") (class "Default")
      (node (ref "Q1") (pin "2") (pinfunction "B_2") (pintype "passive"))
      (node (ref "R6") (pin "1") (pinfunction "1_1") (pintype "passive"))
    )
    (net (code "134") (name "Net-(U1B-OSC_IN)") (class "Default")
      (node (ref "C2") (pin "1") (pintype "passive"))
      (node (ref "R4") (pin "2") (pinfunction "2_2") (pintype "passive"))
      (node (ref "U1") (pin "23") (pinfunction "OSC_IN_23") (pintype "input"))
      (node (ref "Y1") (pin "1") (pinfunction "OSC1_1") (pintype "passive"))
    )
    (net (code "135") (name "Net-(U1B-OSC_OUT)") (class "Default")
      (node (ref "C3") (pin "1") (pintype "passive"))
      (node (ref "R4") (pin "1") (pinfunction "1_1") (pintype "passive"))
      (node (ref "U1") (pin "24") (pinfunction "OSC_OUT_24") (pintype "passive"))
      (node (ref "Y1") (pin "2") (pinfunction "OSC2_2") (pintype "passive"))
    )
    (net (code "136") (name "Net-(U3-EN_A)") (class "Default")
      (node (ref "P12") (pin "2") (pinfunction "2_2") (pintype "passive"))
      (node (ref "U3") (pin "8") (pinfunction "EN_A_8") (pintype "input"))
    )
    (net (code "137") (name "Net-(U3-EN_B)") (class "Default")
      (node (ref "P15") (pin "2") (pinfunction "2_2") (pintype "passive"))
      (node (ref "U3") (pin "14") (pinfunction "EN_B_14") (pintype "input"))
    )
    (net (code "138") (name "Net-(U3-IN1)") (class "Default")
      (node (ref "P9") (pin "2") (pinfunction "2_2") (pintype "passive"))
      (node (ref "U3") (pin "7") (pinfunction "IN1_7") (pintype "input"))
    )
    (net (code "139") (name "Net-(U3-IN2)") (class "Default")
      (node (ref "P9") (pin "4") (pinfunction "4_4") (pintype "passive"))
      (node (ref "U3") (pin "9") (pinfunction "IN2_9") (pintype "input"))
    )
    (net (code "140") (name "Net-(U3-IN3)") (class "Default")
      (node (ref "P9") (pin "6") (pinfunction "6_6") (pintype "passive"))
      (node (ref "U3") (pin "13") (pinfunction "IN3_13") (pintype "input"))
    )
    (net (code "141") (name "Net-(U3-IN4)") (class "Default")
      (node (ref "P9") (pin "8") (pinfunction "8_8") (pintype "passive"))
      (node (ref "U3") (pin "15") (pinfunction "IN4_15") (pintype "input"))
    )
    (net (code "142") (name "Net-(U4-IRQ)") (class "Default")
      (node (ref "R14") (pin "2") (pinfunction "2_2") (pintype "passive"))
      (node (ref "U4") (pin "8") (pinfunction "IRQ_8") (pintype "passive"))
    )
    (net (code "143") (name "VCC3.3") (class "Default")
      (node (ref "C12") (pin "1") (pinfunction "1_1") (pintype "passive"))
      (node (ref "C13") (pin "2") (pintype "passive"))
      (node (ref "C9") (pin "1") (pintype "passive"))
      (node (ref "D12") (pin "1") (pinfunction "A_1") (pintype "passive"))
      (node (ref "P12") (pin "4") (pinfunction "4_4") (pintype "passive"))
      (node (ref "P15") (pin "4") (pinfunction "4_4") (pintype "passive"))
      (node (ref "P16") (pin "3") (pinfunction "3_3") (pintype "passive"))
      (node (ref "P5") (pin "25") (pinfunction "25_25") (pintype "passive"))
      (node (ref "P5") (pin "26") (pinfunction "26_26") (pintype "passive"))
      (node (ref "P5") (pin "27") (pinfunction "27_27") (pintype "passive"))
      (node (ref "P5") (pin "28") (pinfunction "28_28") (pintype "passive"))
      (node (ref "R1") (pin "2") (pinfunction "2_2") (pintype "passive"))
      (node (ref "R2") (pin "2") (pinfunction "2_2") (pintype "passive"))
      (node (ref "R3") (pin "2") (pinfunction "2_2") (pintype "passive"))
      (node (ref "R5") (pin "2") (pinfunction "2_2") (pintype "passive"))
      (node (ref "U1") (pin "108") (pinfunction "VDD_2_108") (pintype "power_in"))
      (node (ref "U1") (pin "121") (pinfunction "VDD_10_121") (pintype "power_in"))
      (node (ref "U1") (pin "131") (pinfunction "VDD_11_131") (pintype "power_in"))
      (node (ref "U1") (pin "144") (pinfunction "VDD_3_144") (pintype "power_in"))
      (node (ref "U1") (pin "17") (pinfunction "VDD_5_17") (pintype "power_in"))
      (node (ref "U1") (pin "33") (pinfunction "VDDA_33") (pintype "power_in"))
      (node (ref "U1") (pin "39") (pinfunction "VDD_4_39") (pintype "power_in"))
      (node (ref "U1") (pin "52") (pinfunction "VDD_6_52") (pintype "power_in"))
      (node (ref "U1") (pin "62") (pinfunction "VDD_7_62") (pintype "power_in"))
      (node (ref "U1") (pin "72") (pinfunction "VDD_1_72") (pintype "power_in"))
      (node (ref "U1") (pin "84") (pinfunction "VDD_8_84") (pintype "power_in"))
      (node (ref "U1") (pin "95") (pinfunction "VDD_9_95") (pintype "power_in"))
      (node (ref "U2") (pin "8") (pinfunction "VCC1_8") (pintype "passive"))
      (node (ref "VR1") (pin "2") (pinfunction "Vout_2") (pintype "passive"))
      (node (ref "WK_UP1") (pin "1") (pinfunction "1_1") (pintype "passive"))
    )
    (net (code "144") (name "VCC3.3T") (class "Default")
      (node (ref "C1") (pin "1") (pintype "passive"))
      (node (ref "C18") (pin "2") (pintype "passive"))
      (node (ref "C20") (pin "1") (pinfunction "1_1") (pintype "passive"))
      (node (ref "C21") (pin "2") (pintype "passive"))
      (node (ref "JTAG") (pin "1") (pinfunction "VDD_1") (pintype "passive"))
      (node (ref "JTAG") (pin "2") (pinfunction "VDD_2") (pintype "passive"))
      (node (ref "LCD1") (pin "24") (pinfunction "VDD3.3_24") (pintype "passive"))
      (node (ref "LCD1") (pin "25") (pinfunction "VDD3.3_25") (pintype "passive"))
      (node (ref "P11") (pin "1") (pinfunction "1_1") (pintype "passive"))
      (node (ref "P18") (pin "1") (pinfunction "1_1") (pintype "passive"))
      (node (ref "P18") (pin "3") (pinfunction "3_3") (pintype "passive"))
      (node (ref "P18") (pin "5") (pinfunction "5_5") (pintype "passive"))
      (node (ref "P18") (pin "7") (pinfunction "7_7") (pintype "passive"))
      (node (ref "R10") (pin "2") (pinfunction "2_2") (pintype "passive"))
      (node (ref "R11") (pin "2") (pinfunction "2_2") (pintype "passive"))
      (node (ref "R13") (pin "2") (pinfunction "2_2") (pintype "passive"))
      (node (ref "R9") (pin "2") (pinfunction "2_2") (pintype "passive"))
      (node (ref "U4") (pin "2") (pinfunction "VCC_2") (pintype "passive"))
      (node (ref "VR3") (pin "2") (pinfunction "Vout_2") (pintype "passive"))
    )
    (net (code "145") (name "VCC5") (class "Default")
      (node (ref "BEEP1") (pin "1") (pinfunction "P_1") (pintype "passive"))
      (node (ref "C10") (pin "2") (pintype "passive"))
      (node (ref "C14") (pin "1") (pinfunction "1_1") (pintype "passive"))
      (node (ref "C15") (pin "2") (pintype "passive"))
      (node (ref "C19") (pin "2") (pintype "passive"))
      (node (ref "C4") (pin "1") (pintype "passive"))
      (node (ref "D14") (pin "2") (pintype "passive"))
      (node (ref "LCD1") (pin "28") (pinfunction "BL_VDD_28") (pintype "passive"))
      (node (ref "P10") (pin "10") (pinfunction "10_10") (pintype "passive"))
      (node (ref "P10") (pin "9") (pinfunction "9_9") (pintype "passive"))
      (node (ref "P14") (pin "1") (pinfunction "1_1") (pintype "passive"))
      (node (ref "P16") (pin "1") (pinfunction "1_1") (pintype "passive"))
      (node (ref "P17") (pin "1") (pinfunction "1_1") (pintype "passive"))
      (node (ref "P17") (pin "3") (pinfunction "3_3") (pintype "passive"))
      (node (ref "P17") (pin "5") (pinfunction "5_5") (pintype "passive"))
      (node (ref "P17") (pin "7") (pinfunction "7_7") (pintype "passive"))
      (node (ref "P8") (pin "1") (pinfunction "1_1") (pintype "passive"))
      (node (ref "U3") (pin "12") (pinfunction "VSS_12") (pintype "power_in"))
      (node (ref "USB") (pin "1") (pinfunction "VCC_1") (pintype "passive"))
      (node (ref "VR1") (pin "3") (pinfunction "Vin_3") (pintype "passive"))
      (node (ref "VR2") (pin "2") (pinfunction "Vout_2") (pintype "passive"))
      (node (ref "VR3") (pin "3") (pinfunction "Vin_3") (pintype "passive"))
    )
    (net (code "146") (name "unconnected-(JTAG-NC-Pad11)") (class "Default")
      (node (ref "JTAG") (pin "11") (pinfunction "NC_11") (pintype "passive"))
    )
    (net (code "147") (name "unconnected-(JTAG-NC-Pad17)") (class "Default")
      (node (ref "JTAG") (pin "17") (pinfunction "NC_17") (pintype "passive"))
    )
    (net (code "148") (name "unconnected-(JTAG-NC-Pad19)") (class "Default")
      (node (ref "JTAG") (pin "19") (pinfunction "NC_19") (pintype "passive"))
    )
    (net (code "149") (name "unconnected-(K1-I{slash}O1-Pad1)") (class "Default")
      (node (ref "K1") (pin "1") (pinfunction "I/O1_1") (pintype "passive"))
    )
    (net (code "150") (name "unconnected-(K1-I{slash}O2-Pad6)") (class "Default")
      (node (ref "K1") (pin "6") (pinfunction "I/O2_6") (pintype "passive"))
    )
    (net (code "151") (name "unconnected-(LCD1-MO-Pad32)") (class "Default")
      (node (ref "LCD1") (pin "32") (pinfunction "MO_32") (pintype "passive"))
    )
    (net (code "152") (name "unconnected-(P3-Pad30)") (class "Default")
      (node (ref "P3") (pin "30") (pinfunction "30_30") (pintype "passive"))
    )
    (net (code "153") (name "unconnected-(P3-Pad31)") (class "Default")
      (node (ref "P3") (pin "31") (pinfunction "31_31") (pintype "passive"))
    )
    (net (code "154") (name "unconnected-(P3-Pad32)") (class "Default")
      (node (ref "P3") (pin "32") (pinfunction "32_32") (pintype "passive"))
    )
    (net (code "155") (name "unconnected-(P4-Pad1)") (class "Default")
      (node (ref "P4") (pin "1") (pinfunction "1_1") (pintype "passive"))
    )
    (net (code "156") (name "unconnected-(P4-Pad2)") (class "Default")
      (node (ref "P4") (pin "2") (pinfunction "2_2") (pintype "passive"))
    )
    (net (code "157") (name "unconnected-(P4-Pad3)") (class "Default")
      (node (ref "P4") (pin "3") (pinfunction "3_3") (pintype "passive"))
    )
    (net (code "158") (name "unconnected-(P6-Pad29)") (class "Default")
      (node (ref "P6") (pin "29") (pinfunction "29_29") (pintype "passive"))
    )
    (net (code "159") (name "unconnected-(P6-Pad30)") (class "Default")
      (node (ref "P6") (pin "30") (pinfunction "30_30") (pintype "passive"))
    )
    (net (code "160") (name "unconnected-(P6-Pad31)") (class "Default")
      (node (ref "P6") (pin "31") (pinfunction "31_31") (pintype "passive"))
    )
    (net (code "161") (name "unconnected-(P6-Pad32)") (class "Default")
      (node (ref "P6") (pin "32") (pinfunction "32_32") (pintype "passive"))
    )
    (net (code "162") (name "unconnected-(P7-Pad1)") (class "Default")
      (node (ref "P7") (pin "1") (pinfunction "1_1") (pintype "passive"))
    )
    (net (code "163") (name "unconnected-(P7-Pad2)") (class "Default")
      (node (ref "P7") (pin "2") (pinfunction "2_2") (pintype "passive"))
    )
    (net (code "164") (name "unconnected-(P7-Pad3)") (class "Default")
      (node (ref "P7") (pin "3") (pinfunction "3_3") (pintype "passive"))
    )
    (net (code "165") (name "unconnected-(P8-Pad2)") (class "Default")
      (node (ref "P8") (pin "2") (pinfunction "2_2") (pintype "passive"))
    )
    (net (code "166") (name "unconnected-(P8-Pad4)") (class "Default")
      (node (ref "P8") (pin "4") (pinfunction "4_4") (pintype "passive"))
    )
    (net (code "167") (name "unconnected-(P8-Pad5)") (class "Default")
      (node (ref "P8") (pin "5") (pinfunction "5_5") (pintype "passive"))
    )
    (net (code "168") (name "unconnected-(P14-Pad3)") (class "Default")
      (node (ref "P14") (pin "3") (pinfunction "3_3") (pintype "passive"))
    )
    (net (code "169") (name "unconnected-(P19-Pad2)") (class "Default")
      (node (ref "P19") (pin "2") (pinfunction "2_2") (pintype "passive"))
    )
    (net (code "170") (name "unconnected-(P19-Pad3)") (class "Default")
      (node (ref "P19") (pin "3") (pinfunction "3_3") (pintype "passive"))
    )
    (net (code "171") (name "unconnected-(U1B-NC-Pad106)") (class "Default")
      (node (ref "U1") (pin "106") (pinfunction "NC_106") (pintype "passive"))
    )
    (net (code "172") (name "unconnected-(U3-NC-Pad3)") (class "Default")
      (node (ref "U3") (pin "3") (pinfunction "NC_3") (pintype "passive"))
    )
    (net (code "173") (name "unconnected-(U3-NC-Pad18)") (class "Default")
      (node (ref "U3") (pin "18") (pinfunction "NC_18") (pintype "passive"))
    )
    (net (code "174") (name "unconnected-(USB-D+-Pad3)") (class "Default")
      (node (ref "USB") (pin "3") (pinfunction "D+_3") (pintype "passive"))
    )
    (net (code "175") (name "unconnected-(USB-D--Pad2)") (class "Default")
      (node (ref "USB") (pin "2") (pinfunction "D-_2") (pintype "passive"))
    )
    (net (code "176") (name "unconnected-(USB-NC-Pad4)") (class "Default")
      (node (ref "USB") (pin "4") (pinfunction "NC_4") (pintype "passive"))
    )
  )
)
